# NODE_MCU_V2.net
KiCad netlist of a schematic drawn in Altium Designer
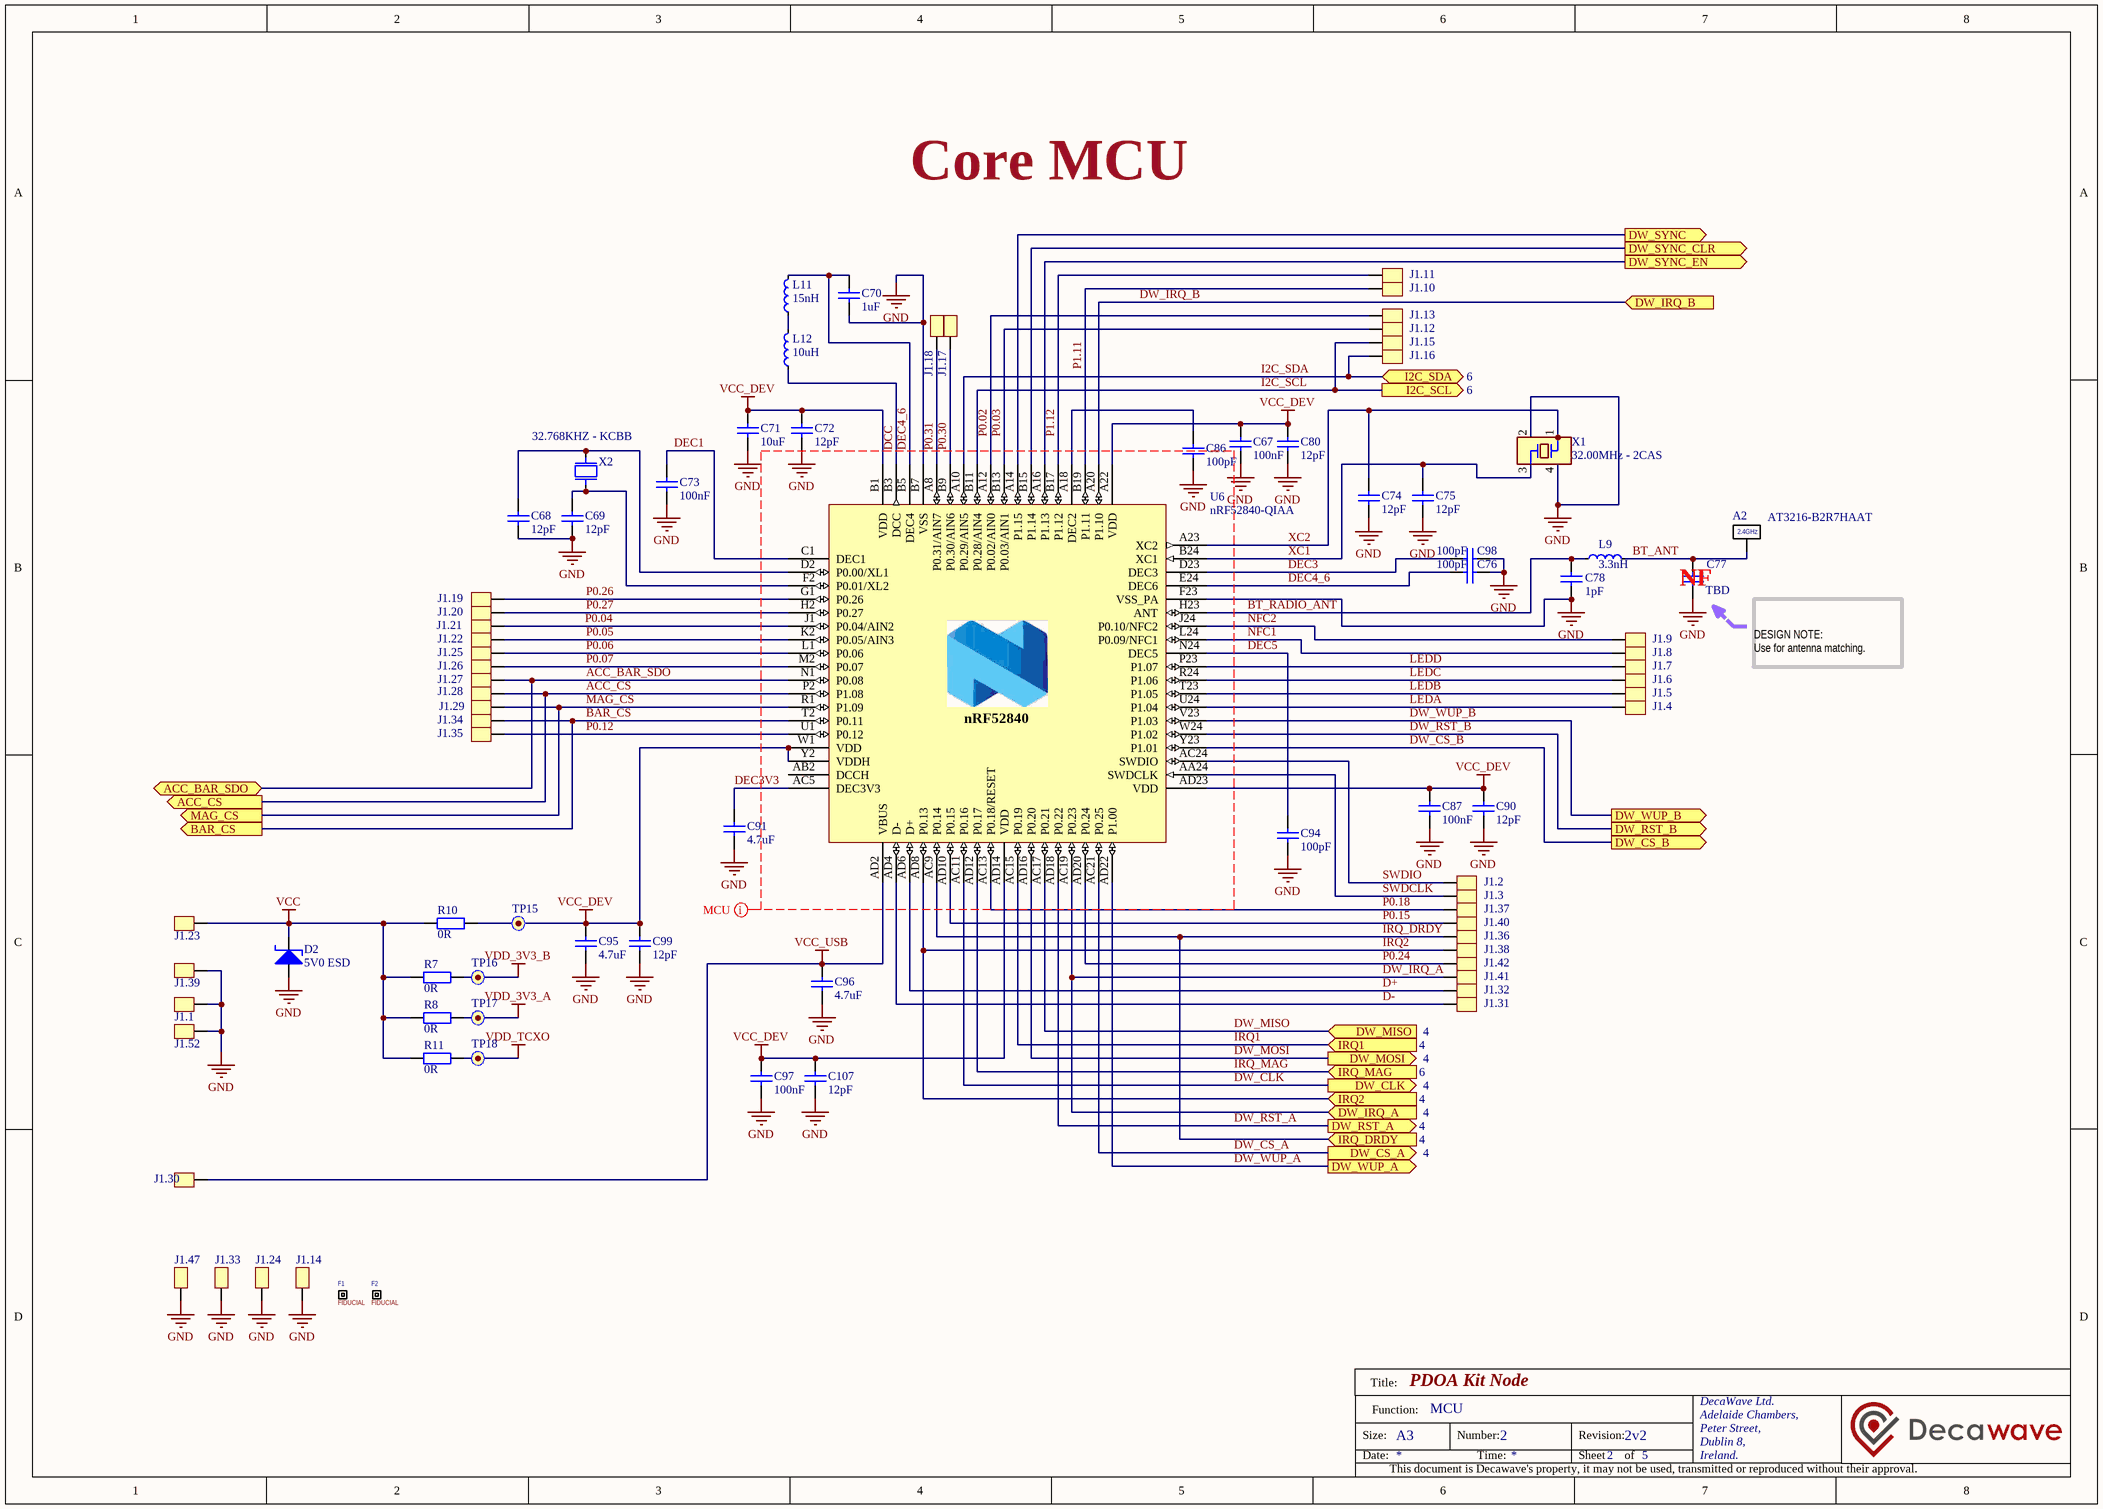
[diagram p0: NODE_MCU_V2.SchDoc]

(export (version "E")
  (design (tool "Eeschema 10.0.6"))
  (components
    (comp (ref "A2")
      (value "AT3216-B2R7HAAT")
      (footprint "AT3216")
      (description "CHIP, 2.45GHZ, 50 OHM, 3.2x1.6 ACX - AAT3216-B2R7HAAT- ANTENNA")
      (fields
        (field (name "MANUFACTURER") "ACX")
        (field (name "MANUFACTURER PART NUMBER") "AMCA31-2R450G-S1F-T")
      )
      (libsource (lib "drak_Library") (part "AT3216-B2R7HAAT"))
    )
    (comp (ref "C67")
      (value "100nF")
      (footprint "C0201")
      (description "100nF_0201_10%")
      (fields
        (field (name "MANUFACTURER") "Murata Electronics North America")
        (field (name "MANUFACTURER PART NUMBER") "GRM033C81E104KE14D")
      )
      (libsource (lib "drak_Library") (part "GRM033C81E104ME14D"))
    )
    (comp (ref "C68")
      (value "12pF")
      (footprint "C0201")
      (description "12pF_0201_1%")
      (fields
        (field (name "MANUFACTURER") "Murata Electronics North America")
        (field (name "MANUFACTURER PART NUMBER") "GRM0335C1E120JA01D")
      )
      (libsource (lib "drak_Library") (part "GRM0335C1E120JA01D"))
    )
    (comp (ref "C69")
      (value "12pF")
      (footprint "C0201")
      (description "12pF_0201_1%")
      (fields
        (field (name "MANUFACTURER") "Murata Electronics North America")
        (field (name "MANUFACTURER PART NUMBER") "GRM0335C1E120JA01D")
      )
      (libsource (lib "drak_Library") (part "GRM0335C1E120JA01D"))
    )
    (comp (ref "C70")
      (value "1uF")
      (footprint "C0402")
      (description "CAP CER 1UF 10V X5R 0402")
      (fields
        (field (name "MANUFACTURER") "Murata Electronics North America")
        (field (name "MANUFACTURER PART NUMBER") "GRM155R61A105KE15D")
      )
      (libsource (lib "drak_Library") (part "GRM155R61A105KE15D"))
    )
    (comp (ref "C71")
      (value "10uF")
      (footprint "C0603")
      (description "CAP CER 10UF 6.3V X5R 0603")
      (fields
        (field (name "MANUFACTURER") "Murata Electronics North America")
        (field (name "MANUFACTURER PART NUMBER") "GRM188R60J106ME47D")
      )
      (libsource (lib "drak_Library") (part "GRM188R60J106ME84D"))
    )
    (comp (ref "C72")
      (value "12pF")
      (footprint "C0201")
      (description "12pF_0201_1%")
      (fields
        (field (name "MANUFACTURER") "Murata Electronics North America")
        (field (name "MANUFACTURER PART NUMBER") "GRM0335C1E120JA01D")
      )
      (libsource (lib "drak_Library") (part "GRM0335C1E120JA01D"))
    )
    (comp (ref "C73")
      (value "100nF")
      (footprint "C0201")
      (description "100nF_0201_10%")
      (fields
        (field (name "MANUFACTURER") "Murata Electronics North America")
        (field (name "MANUFACTURER PART NUMBER") "GRM033C81E104KE14D")
      )
      (libsource (lib "drak_Library") (part "GRM033C81E104ME14D"))
    )
    (comp (ref "C74")
      (value "12pF")
      (footprint "C0201")
      (description "12pF_0201_1%")
      (fields
        (field (name "MANUFACTURER") "Murata Electronics North America")
        (field (name "MANUFACTURER PART NUMBER") "GRM0335C1E120JA01D")
      )
      (libsource (lib "drak_Library") (part "GRM0335C1E120JA01D"))
    )
    (comp (ref "C75")
      (value "12pF")
      (footprint "C0201")
      (description "12pF_0201_1%")
      (fields
        (field (name "MANUFACTURER") "Murata Electronics North America")
        (field (name "MANUFACTURER PART NUMBER") "GRM0335C1E120JA01D")
      )
      (libsource (lib "drak_Library") (part "GRM0335C1E120JA01D"))
    )
    (comp (ref "C76")
      (value "100pF")
      (footprint "C0201")
      (description "CAP CER 100PF 25V NP0 0201")
      (fields
        (field (name "MANUFACTURER") "Murata Electronics North America")
        (field (name "MANUFACTURER PART NUMBER") "GRM0335C1E101JA01D")
      )
      (libsource (lib "drak_Library") (part "GRM0335C1E101JA01D"))
    )
    (comp (ref "C77")
      (value "TBD")
      (footprint "C0201")
      (description "CAP CER 1PF 50V NP0 0201")
      (fields
        (field (name "MANUFACTURER") "Murata Electronics North America")
        (field (name "MANUFACTURER PART NUMBER") "GRM0335C1H1R0BA01D")
      )
      (libsource (lib "drak_Library") (part "GRM0335C1H1R0BA01D"))
    )
    (comp (ref "C78")
      (value "1pF")
      (footprint "C0201")
      (description "CAP CER 1PF 50V NP0 0201")
      (fields
        (field (name "MANUFACTURER") "Murata Electronics North America")
        (field (name "MANUFACTURER PART NUMBER") "GRM0335C1H1R0BA01D")
      )
      (libsource (lib "drak_Library") (part "GRM0335C1H1R0BA01D"))
    )
    (comp (ref "C80")
      (value "12pF")
      (footprint "C0201")
      (description "12pF_0201_1%")
      (fields
        (field (name "MANUFACTURER") "Murata Electronics North America")
        (field (name "MANUFACTURER PART NUMBER") "GRM0335C1E120JA01D")
      )
      (libsource (lib "drak_Library") (part "GRM0335C1E120JA01D"))
    )
    (comp (ref "C86")
      (value "100pF")
      (footprint "C0201")
      (description "CAP CER 100PF 25V NP0 0201")
      (fields
        (field (name "MANUFACTURER") "Murata Electronics North America")
        (field (name "MANUFACTURER PART NUMBER") "GRM0335C1E101JA01D")
      )
      (libsource (lib "drak_Library") (part "GRM0335C1E101JA01D"))
    )
    (comp (ref "C87")
      (value "100nF")
      (footprint "C0201")
      (description "100nF_0201_10%")
      (fields
        (field (name "MANUFACTURER") "Murata Electronics North America")
        (field (name "MANUFACTURER PART NUMBER") "GRM033C81E104KE14D")
      )
      (libsource (lib "drak_Library") (part "GRM033C81E104ME14D"))
    )
    (comp (ref "C90")
      (value "12pF")
      (footprint "C0201")
      (description "12pF_0201_1%")
      (fields
        (field (name "MANUFACTURER") "Murata Electronics North America")
        (field (name "MANUFACTURER PART NUMBER") "GRM0335C1E120JA01D")
      )
      (libsource (lib "drak_Library") (part "GRM0335C1E120JA01D"))
    )
    (comp (ref "C91")
      (value "4.7uF")
      (footprint "C0603")
      (description "CAP CER 4.7UF 6.3V X5R 0603")
      (fields
        (field (name "MANUFACTURER") "SamSung")
        (field (name "MANUFACTURER PART NUMBER") "CL10A475KQ8NNN#")
      )
      (libsource (lib "drak_Library") (part "GRM188R60J106ME84D"))
    )
    (comp (ref "C94")
      (value "100pF")
      (footprint "C0201")
      (description "CAP CER 100PF 25V NP0 0201")
      (fields
        (field (name "MANUFACTURER") "Murata Electronics North America")
        (field (name "MANUFACTURER PART NUMBER") "GRM0335C1E101JA01D")
      )
      (libsource (lib "drak_Library") (part "GRM0335C1E101JA01D"))
    )
    (comp (ref "C95")
      (value "4.7uF")
      (footprint "C0603")
      (description "CAP CER 4.7UF 6.3V X5R 0603")
      (fields
        (field (name "MANUFACTURER") "SamSung")
        (field (name "MANUFACTURER PART NUMBER") "CL10A475KQ8NNN#")
      )
      (libsource (lib "drak_Library") (part "GRM188R60J106ME84D"))
    )
    (comp (ref "C96")
      (value "4.7uF")
      (footprint "C0603")
      (description "CAP CER 4.7UF 6.3V X5R 0603")
      (fields
        (field (name "MANUFACTURER") "SamSung")
        (field (name "MANUFACTURER PART NUMBER") "CL10A475KQ8NNN#")
      )
      (libsource (lib "drak_Library") (part "GRM188R60J106ME84D"))
    )
    (comp (ref "C97")
      (value "100nF")
      (footprint "C0201")
      (description "100nF_0201_10%")
      (fields
        (field (name "MANUFACTURER") "Murata Electronics North America")
        (field (name "MANUFACTURER PART NUMBER") "GRM033C81E104KE14D")
      )
      (libsource (lib "drak_Library") (part "GRM033C81E104ME14D"))
    )
    (comp (ref "C98")
      (value "100pF")
      (footprint "C0201")
      (description "CAP CER 100PF 25V NP0 0201")
      (fields
        (field (name "MANUFACTURER") "Murata Electronics North America")
        (field (name "MANUFACTURER PART NUMBER") "GRM0335C1E101JA01D")
      )
      (libsource (lib "drak_Library") (part "GRM0335C1E101JA01D"))
    )
    (comp (ref "C99")
      (value "12pF")
      (footprint "C0201")
      (description "12pF_0201_1%")
      (fields
        (field (name "MANUFACTURER") "Murata Electronics North America")
        (field (name "MANUFACTURER PART NUMBER") "GRM0335C1E120JA01D")
      )
      (libsource (lib "drak_Library") (part "GRM0335C1E120JA01D"))
    )
    (comp (ref "C107")
      (value "12pF")
      (footprint "C0201")
      (description "12pF_0201_1%")
      (fields
        (field (name "MANUFACTURER") "Murata Electronics North America")
        (field (name "MANUFACTURER PART NUMBER") "GRM0335C1E120JA01D")
      )
      (libsource (lib "drak_Library") (part "GRM0335C1E120JA01D"))
    )
    (comp (ref "D2")
      (value "5V0 ESD")
      (footprint "DFN65P100X40-2N")
      (description "TVS DIODE 5VWM")
      (fields
        (field (name "MANUFACTURER") "Toshiba Semiconductor and Storage")
        (field (name "MANUFACTURER PART NUMBER") "DF2S6.2CT,L3F")
      )
      (libsource (lib "drak_Library") (part "DF2S6.2CT,L3F"))
    )
    (comp (ref "F1")
      (value "FIDUCIAL")
      (footprint "FID1")
      (description "Fiducial 1mm")
      (libsource (lib "drak_Library") (part "FID1"))
    )
    (comp (ref "F2")
      (value "FIDUCIAL")
      (footprint "FID1")
      (description "Fiducial 1mm")
      (libsource (lib "drak_Library") (part "FID1"))
    )
    (comp (ref "J1.1")
      (value "EDGE_PIN")
      (footprint "PCB_EDGE_1MM")
      (description "PCB Edge pin")
      (libsource (lib "DrakSchlib") (part "EDGE_PIN"))
    )
    (comp (ref "J1.2")
      (value "EDGE_PIN")
      (footprint "PCB_EDGE_1MM")
      (description "PCB Edge pin")
      (libsource (lib "") (part "PCB_EDGE_1MM_1"))
    )
    (comp (ref "J1.3")
      (value "EDGE_PIN")
      (footprint "PCB_EDGE_1MM")
      (description "PCB Edge pin")
      (libsource (lib "") (part "PCB_EDGE_1MM_1"))
    )
    (comp (ref "J1.4")
      (value "EDGE_PIN")
      (footprint "PCB_EDGE_1MM")
      (description "PCB Edge pin")
      (libsource (lib "drak_Library") (part "PCB_EDGE_1MM"))
    )
    (comp (ref "J1.5")
      (value "EDGE_PIN")
      (footprint "PCB_EDGE_1MM")
      (description "PCB Edge pin")
      (libsource (lib "drak_Library") (part "PCB_EDGE_1MM"))
    )
    (comp (ref "J1.6")
      (value "EDGE_PIN")
      (footprint "PCB_EDGE_1MM")
      (description "PCB Edge pin")
      (libsource (lib "drak_Library") (part "PCB_EDGE_1MM"))
    )
    (comp (ref "J1.7")
      (value "EDGE_PIN")
      (footprint "PCB_EDGE_1MM")
      (description "PCB Edge pin")
      (libsource (lib "drak_Library") (part "PCB_EDGE_1MM"))
    )
    (comp (ref "J1.8")
      (value "EDGE_PIN")
      (footprint "PCB_EDGE_1MM")
      (description "PCB Edge pin")
      (libsource (lib "") (part "PCB_EDGE_1MM_1"))
    )
    (comp (ref "J1.9")
      (value "EDGE_PIN")
      (footprint "PCB_EDGE_1MM")
      (description "PCB Edge pin")
      (libsource (lib "") (part "PCB_EDGE_1MM_1"))
    )
    (comp (ref "J1.10")
      (value "EDGE_PIN")
      (footprint "PCB_EDGE_1MM")
      (description "PCB Edge pin")
      (libsource (lib "drak_Library") (part "PCB_EDGE_1MM"))
    )
    (comp (ref "J1.11")
      (value "EDGE_PIN")
      (footprint "PCB_EDGE_1MM")
      (description "PCB Edge pin")
      (libsource (lib "drak_Library") (part "PCB_EDGE_1MM"))
    )
    (comp (ref "J1.12")
      (value "EDGE_PIN")
      (footprint "PCB_EDGE_1MM")
      (description "PCB Edge pin")
      (libsource (lib "drak_Library") (part "PCB_EDGE_1MM"))
    )
    (comp (ref "J1.13")
      (value "EDGE_PIN")
      (footprint "PCB_EDGE_1MM")
      (description "PCB Edge pin")
      (libsource (lib "drak_Library") (part "PCB_EDGE_1MM"))
    )
    (comp (ref "J1.14")
      (value "EDGE_PIN")
      (footprint "PCB_EDGE_1MM")
      (description "PCB Edge pin")
      (libsource (lib "drak_Library") (part "PCB_EDGE_1MM"))
    )
    (comp (ref "J1.15")
      (value "EDGE_PIN")
      (footprint "PCB_EDGE_1MM")
      (description "PCB Edge pin")
      (libsource (lib "drak_Library") (part "PCB_EDGE_1MM"))
    )
    (comp (ref "J1.16")
      (value "EDGE_PIN")
      (footprint "PCB_EDGE_1MM")
      (description "PCB Edge pin")
      (libsource (lib "drak_Library") (part "PCB_EDGE_1MM"))
    )
    (comp (ref "J1.17")
      (value "EDGE_PIN")
      (footprint "PCB_EDGE_1MM")
      (description "PCB Edge pin")
      (libsource (lib "drak_Library") (part "PCB_EDGE_1MM"))
    )
    (comp (ref "J1.18")
      (value "EDGE_PIN")
      (footprint "PCB_EDGE_1MM")
      (description "PCB Edge pin")
      (libsource (lib "drak_Library") (part "PCB_EDGE_1MM"))
    )
    (comp (ref "J1.19")
      (value "EDGE_PIN")
      (footprint "PCB_EDGE_1MM")
      (description "PCB Edge pin")
      (libsource (lib "DrakSchlib") (part "EDGE_PIN"))
    )
    (comp (ref "J1.20")
      (value "EDGE_PIN")
      (footprint "PCB_EDGE_1MM")
      (description "PCB Edge pin")
      (libsource (lib "") (part "PCB_EDGE_1MM_3"))
    )
    (comp (ref "J1.21")
      (value "EDGE_PIN")
      (footprint "PCB_EDGE_1MM")
      (description "PCB Edge pin")
      (libsource (lib "") (part "PCB_EDGE_1MM_2"))
    )
    (comp (ref "J1.22")
      (value "EDGE_PIN")
      (footprint "PCB_EDGE_1MM")
      (description "PCB Edge pin")
      (libsource (lib "DrakSchlib") (part "EDGE_PIN"))
    )
    (comp (ref "J1.23")
      (value "EDGE_PIN")
      (footprint "PCB_EDGE_1MM")
      (description "PCB Edge pin")
      (libsource (lib "DrakSchlib") (part "EDGE_PIN"))
    )
    (comp (ref "J1.24")
      (value "EDGE_PIN")
      (footprint "PCB_EDGE_1MM")
      (description "PCB Edge pin")
      (libsource (lib "drak_Library") (part "PCB_EDGE_1MM"))
    )
    (comp (ref "J1.25")
      (value "EDGE_PIN")
      (footprint "PCB_EDGE_1MM")
      (description "PCB Edge pin")
      (libsource (lib "") (part "PCB_EDGE_1MM_2"))
    )
    (comp (ref "J1.26")
      (value "EDGE_PIN")
      (footprint "PCB_EDGE_1MM")
      (description "PCB Edge pin")
      (libsource (lib "") (part "PCB_EDGE_1MM_3"))
    )
    (comp (ref "J1.27")
      (value "EDGE_PIN")
      (footprint "PCB_EDGE_1MM")
      (description "PCB Edge pin")
      (libsource (lib "") (part "PCB_EDGE_1MM_3"))
    )
    (comp (ref "J1.28")
      (value "EDGE_PIN")
      (footprint "PCB_EDGE_1MM")
      (description "PCB Edge pin")
      (libsource (lib "") (part "PCB_EDGE_1MM_2"))
    )
    (comp (ref "J1.29")
      (value "EDGE_PIN")
      (footprint "PCB_EDGE_1MM")
      (description "PCB Edge pin")
      (libsource (lib "") (part "PCB_EDGE_1MM_2"))
    )
    (comp (ref "J1.30")
      (value "EDGE_PIN")
      (footprint "PCB_EDGE_1MM")
      (description "PCB Edge pin")
      (libsource (lib "DrakSchlib") (part "EDGE_PIN"))
    )
    (comp (ref "J1.31")
      (value "EDGE_PIN")
      (footprint "PCB_EDGE_1MM")
      (description "PCB Edge pin")
      (libsource (lib "") (part "PCB_EDGE_1MM_1"))
    )
    (comp (ref "J1.32")
      (value "EDGE_PIN")
      (footprint "PCB_EDGE_1MM")
      (description "PCB Edge pin")
      (libsource (lib "") (part "PCB_EDGE_1MM_1"))
    )
    (comp (ref "J1.33")
      (value "EDGE_PIN")
      (footprint "PCB_EDGE_1MM")
      (description "PCB Edge pin")
      (libsource (lib "drak_Library") (part "PCB_EDGE_1MM"))
    )
    (comp (ref "J1.34")
      (value "EDGE_PIN")
      (footprint "PCB_EDGE_1MM")
      (description "PCB Edge pin")
      (libsource (lib "") (part "PCB_EDGE_1MM_2"))
    )
    (comp (ref "J1.35")
      (value "EDGE_PIN")
      (footprint "PCB_EDGE_1MM")
      (description "PCB Edge pin")
      (libsource (lib "DrakSchlib") (part "EDGE_PIN"))
    )
    (comp (ref "J1.36")
      (value "EDGE_PIN")
      (footprint "PCB_EDGE_1MM")
      (description "PCB Edge pin")
      (libsource (lib "") (part "PCB_EDGE_1MM_1"))
    )
    (comp (ref "J1.37")
      (value "EDGE_PIN")
      (footprint "PCB_EDGE_1MM")
      (description "PCB Edge pin")
      (libsource (lib "") (part "PCB_EDGE_1MM_1"))
    )
    (comp (ref "J1.38")
      (value "EDGE_PIN")
      (footprint "PCB_EDGE_1MM")
      (description "PCB Edge pin")
      (libsource (lib "") (part "PCB_EDGE_1MM_1"))
    )
    (comp (ref "J1.39")
      (value "EDGE_PIN")
      (footprint "PCB_EDGE_1MM")
      (description "PCB Edge pin")
      (libsource (lib "DrakSchlib") (part "EDGE_PIN"))
    )
    (comp (ref "J1.40")
      (value "EDGE_PIN")
      (footprint "PCB_EDGE_1MM")
      (description "PCB Edge pin")
      (libsource (lib "") (part "PCB_EDGE_1MM_1"))
    )
    (comp (ref "J1.41")
      (value "EDGE_PIN")
      (footprint "PCB_EDGE_1MM")
      (description "PCB Edge pin")
      (libsource (lib "") (part "PCB_EDGE_1MM_1"))
    )
    (comp (ref "J1.42")
      (value "EDGE_PIN")
      (footprint "PCB_EDGE_1MM")
      (description "PCB Edge pin")
      (libsource (lib "") (part "PCB_EDGE_1MM_1"))
    )
    (comp (ref "J1.47")
      (value "EDGE_PIN")
      (footprint "PCB_EDGE_1MM")
      (description "PCB Edge pin")
      (libsource (lib "drak_Library") (part "PCB_EDGE_1MM"))
    )
    (comp (ref "J1.52")
      (value "EDGE_PIN")
      (footprint "PCB_EDGE_1MM")
      (description "PCB Edge pin")
      (libsource (lib "DrakSchlib") (part "EDGE_PIN"))
    )
    (comp (ref "L9")
      (value "3.3nH")
      (footprint "L0201")
      (description "FIXED IND 3.3NH 400MA 320 MOHM")
      (fields
        (field (name "MANUFACTURER") "Murata Electronics North America")
        (field (name "MANUFACTURER PART NUMBER") "LQP03TG3N3C02D")
      )
      (libsource (lib "drak_Library") (part "LQP03TG3N3C02D"))
    )
    (comp (ref "L11")
      (value "15nH")
      (footprint "INDC1005X05N")
      (description "FIXED IND 15NH 320MA 460 MOHM")
      (fields
        (field (name "MANUFACTURER") "Taiyo Yuden")
        (field (name "MANUFACTURER PART NUMBER") "HK100515NJ-T")
      )
      (libsource (lib "Schlib1") (part "HK100515NJ-T"))
    )
    (comp (ref "L12")
      (value "10uH")
      (footprint "L0603")
      (description "FIXED IND 10UH 80MA 360 MOHM SMD")
      (fields
        (field (name "MANUFACTURER") "Taiyo Yuden")
        (field (name "MANUFACTURER PART NUMBER") "LBMF1608T100K")
      )
      (libsource (lib "drak_Library") (part "LBMF1608T100K"))
    )
    (comp (ref "R7")
      (value "0R")
      (footprint "R0201")
      (description "RES SMD 0.0OHM JUMPER 1/20W 0201")
      (fields
        (field (name "MANUFACTURER") "Yageo")
        (field (name "MANUFACTURER PART NUMBER") "RC0201JR-070RL")
      )
      (libsource (lib "drak_Library") (part "RC0201JR-070RL"))
    )
    (comp (ref "R8")
      (value "0R")
      (footprint "R0402 -RF")
      (description "RES SMD 0.0OHM JUMPER 1/20W 0402")
      (fields
        (field (name "MANUFACTURER") "Yageo")
        (field (name "MANUFACTURER PART NUMBER") "RC0402JR-070RL")
      )
      (libsource (lib "drak_Library") (part "RC0201JR-070RL"))
    )
    (comp (ref "R10")
      (value "0R")
      (footprint "R0201")
      (description "RES SMD 0.0OHM JUMPER 1/20W 0201")
      (fields
        (field (name "MANUFACTURER") "Yageo")
        (field (name "MANUFACTURER PART NUMBER") "RC0201JR-070RL")
      )
      (libsource (lib "drak_Library") (part "RC0201JR-070RL"))
    )
    (comp (ref "R11")
      (value "0R")
      (footprint "R0201")
      (description "RES SMD 0.0OHM JUMPER 1/20W 0201")
      (fields
        (field (name "MANUFACTURER") "Yageo")
        (field (name "MANUFACTURER PART NUMBER") "RC0201JR-070RL")
      )
      (libsource (lib "drak_Library") (part "RC0201JR-070RL"))
    )
    (comp (ref "TP15")
      (value "TP")
      (footprint "TP_40S")
      (description "test point")
      (libsource (lib "AoAB") (part "TP"))
    )
    (comp (ref "TP16")
      (value "TP")
      (footprint "TP_40S")
      (description "test point")
      (libsource (lib "AoAB") (part "TP"))
    )
    (comp (ref "TP17")
      (value "TP")
      (footprint "TP_40S")
      (description "test point")
      (libsource (lib "AoAB") (part "TP"))
    )
    (comp (ref "TP18")
      (value "TP")
      (footprint "TP_40S")
      (description "test point")
      (libsource (lib "AoAB") (part "TP"))
    )
    (comp (ref "U6")
      (value "nRF52840-QIAA")
      (footprint "AQFN50P700X700X85_HS-74N")
      (description "Multi-protocol Bluetooth Low Energy, IEEE 802.15.4, ANT and 2.4GHz proprietary system-on-chip")
      (fields (field (name "MANUFACTURER") "Nordic Semiconductor ASA"))
      (libsource (lib "NODE_V2") (part "nRF52840_QIAA"))
    )
    (comp (ref "X1")
      (value "32.00MHz - 2CAS")
      (footprint "ABM10")
      (description "CRYSTAL 32MHZ 8PF SMD")
      (fields (field (name "MANUFACTURER") "Commutek") (field (name "MANUFACTURER PART NUMBER") "2CAS"))
      (libsource (lib "drak_Library") (part "ABM10"))
    )
    (comp (ref "X2")
      (value "32.768KHZ - KCBB")
      (footprint "XTAL_SMD_3.2X1.5MM")
      (description "CRYSTAL 32.7680KHZ 12.5PF SMD")
      (fields (field (name "MANUFACTURER") "Commutek") (field (name "MANUFACTURER PART NUMBER") "KCBB"))
      (libsource (lib "drak_Library") (part "ABS06-32.768KHZ-T"))
    )
  )
  (nets
    (net (code "1") (name "/ACC_BAR_SDO") (class "Default")
      (node (ref "J1.27") (pin "0") (pinfunction "0_0") (pintype "passive"))
      (node (ref "U6") (pin "N1") (pinfunction "P0.08_N1") (pintype "bidirectional"))
    )
    (net (code "2") (name "/ACC_CS") (class "Default")
      (node (ref "J1.28") (pin "0") (pinfunction "0_0") (pintype "passive"))
      (node (ref "U6") (pin "P2") (pinfunction "P1.08_P2") (pintype "bidirectional"))
    )
    (net (code "3") (name "/BAR_CS") (class "Default")
      (node (ref "J1.34") (pin "0") (pinfunction "0_0") (pintype "passive"))
      (node (ref "U6") (pin "T2") (pinfunction "P0.11_T2") (pintype "bidirectional"))
    )
    (net (code "4") (name "/BT_ANT") (class "Default")
      (node (ref "A2") (pin "1") (pintype "passive"))
      (node (ref "C77") (pin "2") (pinfunction "2_2") (pintype "passive"))
      (node (ref "L9") (pin "2") (pinfunction "2_2") (pintype "passive"))
    )
    (net (code "5") (name "/BT_RADIO_ANT") (class "Default")
      (node (ref "C78") (pin "2") (pinfunction "2_2") (pintype "passive"))
      (node (ref "L9") (pin "1") (pinfunction "1_1") (pintype "passive"))
      (node (ref "U6") (pin "H23") (pinfunction "ANT_H23") (pintype "bidirectional"))
    )
    (net (code "6") (name "/D+") (class "Default")
      (node (ref "J1.32") (pin "0") (pinfunction "0_0") (pintype "passive"))
      (node (ref "U6") (pin "AD6") (pinfunction "D+_AD6") (pintype "bidirectional"))
    )
    (net (code "7") (name "/D-") (class "Default")
      (node (ref "J1.31") (pin "0") (pinfunction "0_0") (pintype "passive"))
      (node (ref "U6") (pin "AD4") (pinfunction "D-_AD4") (pintype "bidirectional"))
    )
    (net (code "8") (name "/DCC") (class "Default")
      (node (ref "L12") (pin "1") (pinfunction "1_1") (pintype "passive"))
      (node (ref "U6") (pin "B3") (pinfunction "DCC_B3") (pintype "output"))
    )
    (net (code "9") (name "/DEC1") (class "Default")
      (node (ref "C73") (pin "2") (pinfunction "2_2") (pintype "passive"))
      (node (ref "U6") (pin "C1") (pinfunction "DEC1_C1") (pintype "power_in"))
    )
    (net (code "10") (name "/DEC3") (class "Default")
      (node (ref "C98") (pin "2") (pinfunction "2_2") (pintype "passive"))
      (node (ref "U6") (pin "D23") (pinfunction "DEC3_D23") (pintype "power_in"))
    )
    (net (code "11") (name "/DEC3V3") (class "Default")
      (node (ref "C91") (pin "2") (pinfunction "2_2") (pintype "passive"))
      (node (ref "U6") (pin "AC5") (pinfunction "DEC3V3_AC5") (pintype "power_in"))
    )
    (net (code "12") (name "/DEC4_6") (class "Default")
      (node (ref "C70") (pin "2") (pinfunction "2_2") (pintype "passive"))
      (node (ref "C76") (pin "2") (pinfunction "2_2") (pintype "passive"))
      (node (ref "L11") (pin "2") (pinfunction "2_2") (pintype "passive"))
      (node (ref "U6") (pin "B5") (pinfunction "DEC4_B5") (pintype "power_in"))
      (node (ref "U6") (pin "E24") (pinfunction "DEC6_E24") (pintype "power_in"))
    )
    (net (code "13") (name "/DEC5") (class "Default")
      (node (ref "C94") (pin "2") (pinfunction "2_2") (pintype "passive"))
      (node (ref "U6") (pin "N24") (pinfunction "DEC5_N24") (pintype "power_in"))
    )
    (net (code "14") (name "/DW_CLK") (class "Default")
      (node (ref "U6") (pin "AC11") (pinfunction "P0.16_AC11") (pintype "bidirectional"))
    )
    (net (code "15") (name "/DW_CS_A") (class "Default")
      (node (ref "U6") (pin "AC21") (pinfunction "P0.25_AC21") (pintype "bidirectional"))
    )
    (net (code "16") (name "/DW_CS_B") (class "Default")
      (node (ref "U6") (pin "Y23") (pinfunction "P1.01_Y23") (pintype "bidirectional"))
    )
    (net (code "17") (name "/DW_IRQ_A") (class "Default")
      (node (ref "J1.41") (pin "0") (pinfunction "0_0") (pintype "passive"))
      (node (ref "U6") (pin "AC19") (pinfunction "P0.23_AC19") (pintype "bidirectional"))
    )
    (net (code "18") (name "/DW_IRQ_B") (class "Default")
      (node (ref "U6") (pin "A20") (pinfunction "P1.10_A20") (pintype "bidirectional"))
    )
    (net (code "19") (name "/DW_MISO") (class "Default")
      (node (ref "U6") (pin "AC17") (pinfunction "P0.21_AC17") (pintype "bidirectional"))
    )
    (net (code "20") (name "/DW_MOSI") (class "Default")
      (node (ref "U6") (pin "AD16") (pinfunction "P0.20_AD16") (pintype "bidirectional"))
    )
    (net (code "21") (name "/DW_RST_A") (class "Default")
      (node (ref "U6") (pin "AD18") (pinfunction "P0.22_AD18") (pintype "bidirectional"))
    )
    (net (code "22") (name "/DW_RST_B") (class "Default")
      (node (ref "U6") (pin "W24") (pinfunction "P1.02_W24") (pintype "bidirectional"))
    )
    (net (code "23") (name "/DW_SYNC") (class "Default")
      (node (ref "U6") (pin "A14") (pinfunction "P1.15_A14") (pintype "bidirectional"))
    )
    (net (code "24") (name "/DW_SYNC_CLR") (class "Default")
      (node (ref "U6") (pin "B15") (pinfunction "P1.14_B15") (pintype "bidirectional"))
    )
    (net (code "25") (name "/DW_SYNC_EN") (class "Default")
      (node (ref "U6") (pin "A16") (pinfunction "P1.13_A16") (pintype "bidirectional"))
    )
    (net (code "26") (name "/DW_WUP_A") (class "Default")
      (node (ref "U6") (pin "AD22") (pinfunction "P1.00_AD22") (pintype "bidirectional"))
    )
    (net (code "27") (name "/DW_WUP_B") (class "Default")
      (node (ref "U6") (pin "V23") (pinfunction "P1.03_V23") (pintype "bidirectional"))
    )
    (net (code "28") (name "/I2C_SCL") (class "Default")
      (node (ref "J1.15") (pin "0") (pinfunction "0_0") (pintype "passive"))
      (node (ref "U6") (pin "B11") (pinfunction "P0.28/AIN4_B11") (pintype "bidirectional"))
    )
    (net (code "29") (name "/I2C_SDA") (class "Default")
      (node (ref "J1.16") (pin "0") (pinfunction "0_0") (pintype "passive"))
      (node (ref "U6") (pin "A10") (pinfunction "P0.29/AIN5_A10") (pintype "bidirectional"))
    )
    (net (code "30") (name "/IRQ1") (class "Default")
      (node (ref "U6") (pin "AC15") (pinfunction "P0.19_AC15") (pintype "bidirectional"))
    )
    (net (code "31") (name "/IRQ2") (class "Default")
      (node (ref "J1.38") (pin "0") (pinfunction "0_0") (pintype "passive"))
      (node (ref "U6") (pin "AD8") (pinfunction "P0.13_AD8") (pintype "bidirectional"))
    )
    (net (code "32") (name "/IRQ_DRDY") (class "Default")
      (node (ref "J1.36") (pin "0") (pinfunction "0_0") (pintype "passive"))
      (node (ref "U6") (pin "AC9") (pinfunction "P0.14_AC9") (pintype "bidirectional"))
    )
    (net (code "33") (name "/IRQ_MAG") (class "Default")
      (node (ref "U6") (pin "AD12") (pinfunction "P0.17_AD12") (pintype "bidirectional"))
    )
    (net (code "34") (name "/LEDA") (class "Default")
      (node (ref "J1.4") (pin "0") (pinfunction "0_0") (pintype "passive"))
      (node (ref "U6") (pin "U24") (pinfunction "P1.04_U24") (pintype "bidirectional"))
    )
    (net (code "35") (name "/LEDB") (class "Default")
      (node (ref "J1.5") (pin "0") (pinfunction "0_0") (pintype "passive"))
      (node (ref "U6") (pin "T23") (pinfunction "P1.05_T23") (pintype "bidirectional"))
    )
    (net (code "36") (name "/LEDC") (class "Default")
      (node (ref "J1.6") (pin "0") (pinfunction "0_0") (pintype "passive"))
      (node (ref "U6") (pin "R24") (pinfunction "P1.06_R24") (pintype "bidirectional"))
    )
    (net (code "37") (name "/LEDD") (class "Default")
      (node (ref "J1.7") (pin "0") (pinfunction "0_0") (pintype "passive"))
      (node (ref "U6") (pin "P23") (pinfunction "P1.07_P23") (pintype "bidirectional"))
    )
    (net (code "38") (name "/MAG_CS") (class "Default")
      (node (ref "J1.29") (pin "0") (pinfunction "0_0") (pintype "passive"))
      (node (ref "U6") (pin "R1") (pinfunction "P1.09_R1") (pintype "bidirectional"))
    )
    (net (code "39") (name "/NFC1") (class "Default")
      (node (ref "J1.8") (pin "0") (pinfunction "0_0") (pintype "passive"))
      (node (ref "U6") (pin "L24") (pinfunction "P0.09/NFC1_L24") (pintype "bidirectional"))
    )
    (net (code "40") (name "/NFC2") (class "Default")
      (node (ref "J1.9") (pin "0") (pinfunction "0_0") (pintype "passive"))
      (node (ref "U6") (pin "J24") (pinfunction "P0.10/NFC2_J24") (pintype "bidirectional"))
    )
    (net (code "41") (name "/P0.02") (class "Default")
      (node (ref "J1.13") (pin "0") (pinfunction "0_0") (pintype "passive"))
      (node (ref "U6") (pin "A12") (pinfunction "P0.02/AIN0_A12") (pintype "bidirectional"))
    )
    (net (code "42") (name "/P0.03") (class "Default")
      (node (ref "J1.12") (pin "0") (pinfunction "0_0") (pintype "passive"))
      (node (ref "U6") (pin "B13") (pinfunction "P0.03/AIN1_B13") (pintype "bidirectional"))
    )
    (net (code "43") (name "/P0.04") (class "Default")
      (node (ref "J1.21") (pin "0") (pinfunction "0_0") (pintype "passive"))
      (node (ref "U6") (pin "J1") (pinfunction "P0.04/AIN2_J1") (pintype "bidirectional"))
    )
    (net (code "44") (name "/P0.05") (class "Default")
      (node (ref "J1.22") (pin "0") (pinfunction "0_0") (pintype "passive"))
      (node (ref "U6") (pin "K2") (pinfunction "P0.05/AIN3_K2") (pintype "bidirectional"))
    )
    (net (code "45") (name "/P0.06") (class "Default")
      (node (ref "J1.25") (pin "0") (pinfunction "0_0") (pintype "passive"))
      (node (ref "U6") (pin "L1") (pinfunction "P0.06_L1") (pintype "bidirectional"))
    )
    (net (code "46") (name "/P0.07") (class "Default")
      (node (ref "J1.26") (pin "0") (pinfunction "0_0") (pintype "passive"))
      (node (ref "U6") (pin "M2") (pinfunction "P0.07_M2") (pintype "bidirectional"))
    )
    (net (code "47") (name "/P0.12") (class "Default")
      (node (ref "J1.35") (pin "0") (pinfunction "0_0") (pintype "passive"))
      (node (ref "U6") (pin "U1") (pinfunction "P0.12_U1") (pintype "bidirectional"))
    )
    (net (code "48") (name "/P0.15") (class "Default")
      (node (ref "J1.40") (pin "0") (pinfunction "0_0") (pintype "passive"))
      (node (ref "U6") (pin "AD10") (pinfunction "P0.15_AD10") (pintype "bidirectional"))
    )
    (net (code "49") (name "/P0.18") (class "Default")
      (node (ref "J1.37") (pin "0") (pinfunction "0_0") (pintype "passive"))
      (node (ref "U6") (pin "AC13") (pinfunction "P0.18/RESET_AC13") (pintype "bidirectional"))
    )
    (net (code "50") (name "/P0.24") (class "Default")
      (node (ref "J1.42") (pin "0") (pinfunction "0_0") (pintype "passive"))
      (node (ref "U6") (pin "AD20") (pinfunction "P0.24_AD20") (pintype "bidirectional"))
    )
    (net (code "51") (name "/P0.26") (class "Default")
      (node (ref "J1.19") (pin "0") (pinfunction "0_0") (pintype "passive"))
      (node (ref "U6") (pin "G1") (pinfunction "P0.26_G1") (pintype "bidirectional"))
    )
    (net (code "52") (name "/P0.27") (class "Default")
      (node (ref "J1.20") (pin "0") (pinfunction "0_0") (pintype "passive"))
      (node (ref "U6") (pin "H2") (pinfunction "P0.27_H2") (pintype "bidirectional"))
    )
    (net (code "53") (name "/P0.30") (class "Default")
      (node (ref "J1.17") (pin "0") (pinfunction "0_0") (pintype "passive"))
      (node (ref "U6") (pin "B9") (pinfunction "P0.30/AIN6_B9") (pintype "bidirectional"))
    )
    (net (code "54") (name "/P0.31") (class "Default")
      (node (ref "J1.18") (pin "0") (pinfunction "0_0") (pintype "passive"))
      (node (ref "U6") (pin "A8") (pinfunction "P0.31/AIN7_A8") (pintype "bidirectional"))
    )
    (net (code "55") (name "/P1.11") (class "Default")
      (node (ref "J1.10") (pin "0") (pinfunction "0_0") (pintype "passive"))
      (node (ref "U6") (pin "B19") (pinfunction "P1.11_B19") (pintype "bidirectional"))
    )
    (net (code "56") (name "/P1.12") (class "Default")
      (node (ref "J1.11") (pin "0") (pinfunction "0_0") (pintype "passive"))
      (node (ref "U6") (pin "B17") (pinfunction "P1.12_B17") (pintype "bidirectional"))
    )
    (net (code "57") (name "/SWDCLK") (class "Default")
      (node (ref "J1.3") (pin "0") (pinfunction "0_0") (pintype "passive"))
      (node (ref "U6") (pin "AA24") (pinfunction "SWDCLK_AA24") (pintype "input"))
    )
    (net (code "58") (name "/SWDIO") (class "Default")
      (node (ref "J1.2") (pin "0") (pinfunction "0_0") (pintype "passive"))
      (node (ref "U6") (pin "AC24") (pinfunction "SWDIO_AC24") (pintype "bidirectional"))
    )
    (net (code "59") (name "/XC1") (class "Default")
      (node (ref "C75") (pin "2") (pinfunction "2_2") (pintype "passive"))
      (node (ref "U6") (pin "B24") (pinfunction "XC1_B24") (pintype "input"))
      (node (ref "X1") (pin "3") (pinfunction "3_3") (pintype "passive"))
    )
    (net (code "60") (name "/XC2") (class "Default")
      (node (ref "C74") (pin "2") (pinfunction "2_2") (pintype "passive"))
      (node (ref "U6") (pin "A23") (pinfunction "XC2_A23") (pintype "output"))
      (node (ref "X1") (pin "1") (pinfunction "1_1") (pintype "passive"))
    )
    (net (code "61") (name "GND") (class "Default")
      (node (ref "C107") (pin "1") (pinfunction "1_1") (pintype "passive"))
      (node (ref "C67") (pin "1") (pinfunction "1_1") (pintype "passive"))
      (node (ref "C68") (pin "1") (pinfunction "1_1") (pintype "passive"))
      (node (ref "C69") (pin "1") (pinfunction "1_1") (pintype "passive"))
      (node (ref "C70") (pin "1") (pinfunction "1_1") (pintype "passive"))
      (node (ref "C71") (pin "1") (pinfunction "1_1") (pintype "passive"))
      (node (ref "C72") (pin "1") (pinfunction "1_1") (pintype "passive"))
      (node (ref "C73") (pin "1") (pinfunction "1_1") (pintype "passive"))
      (node (ref "C74") (pin "1") (pinfunction "1_1") (pintype "passive"))
      (node (ref "C75") (pin "1") (pinfunction "1_1") (pintype "passive"))
      (node (ref "C76") (pin "1") (pinfunction "1_1") (pintype "passive"))
      (node (ref "C77") (pin "1") (pinfunction "1_1") (pintype "passive"))
      (node (ref "C78") (pin "1") (pinfunction "1_1") (pintype "passive"))
      (node (ref "C80") (pin "1") (pinfunction "1_1") (pintype "passive"))
      (node (ref "C86") (pin "1") (pinfunction "1_1") (pintype "passive"))
      (node (ref "C87") (pin "1") (pinfunction "1_1") (pintype "passive"))
      (node (ref "C90") (pin "1") (pinfunction "1_1") (pintype "passive"))
      (node (ref "C91") (pin "1") (pinfunction "1_1") (pintype "passive"))
      (node (ref "C94") (pin "1") (pinfunction "1_1") (pintype "passive"))
      (node (ref "C95") (pin "1") (pinfunction "1_1") (pintype "passive"))
      (node (ref "C96") (pin "1") (pinfunction "1_1") (pintype "passive"))
      (node (ref "C97") (pin "1") (pinfunction "1_1") (pintype "passive"))
      (node (ref "C98") (pin "1") (pinfunction "1_1") (pintype "passive"))
      (node (ref "C99") (pin "1") (pinfunction "1_1") (pintype "passive"))
      (node (ref "D2") (pin "A") (pinfunction "A_A") (pintype "passive"))
      (node (ref "J1.1") (pin "0") (pinfunction "0_0") (pintype "passive"))
      (node (ref "J1.14") (pin "0") (pinfunction "0_0") (pintype "passive"))
      (node (ref "J1.24") (pin "0") (pinfunction "0_0") (pintype "passive"))
      (node (ref "J1.33") (pin "0") (pinfunction "0_0") (pintype "passive"))
      (node (ref "J1.39") (pin "0") (pinfunction "0_0") (pintype "passive"))
      (node (ref "J1.47") (pin "0") (pinfunction "0_0") (pintype "passive"))
      (node (ref "J1.52") (pin "0") (pinfunction "0_0") (pintype "passive"))
      (node (ref "U6") (pin "74") (pinfunction "GND_74") (pintype "power_in"))
      (node (ref "U6") (pin "B7") (pinfunction "VSS_B7") (pintype "power_in"))
      (node (ref "U6") (pin "F23") (pinfunction "VSS_PA_F23") (pintype "power_in"))
      (node (ref "X1") (pin "2") (pinfunction "2_2") (pintype "passive"))
      (node (ref "X1") (pin "4") (pinfunction "4_4") (pintype "passive"))
    )
    (net (code "62") (name "Net-(L11-Pad1)") (class "Default")
      (node (ref "L11") (pin "1") (pinfunction "1_1") (pintype "passive"))
      (node (ref "L12") (pin "2") (pinfunction "2_2") (pintype "passive"))
    )
    (net (code "63") (name "Net-(U6-DEC2)") (class "Default")
      (node (ref "C86") (pin "2") (pinfunction "2_2") (pintype "passive"))
      (node (ref "U6") (pin "A18") (pinfunction "DEC2_A18") (pintype "power_in"))
    )
    (net (code "64") (name "Net-(U6-P0.00{slash}XL1)") (class "Default")
      (node (ref "C68") (pin "2") (pinfunction "2_2") (pintype "passive"))
      (node (ref "U6") (pin "D2") (pinfunction "P0.00/XL1_D2") (pintype "bidirectional"))
      (node (ref "X2") (pin "2") (pinfunction "2_2") (pintype "passive"))
    )
    (net (code "65") (name "Net-(U6-P0.01{slash}XL2)") (class "Default")
      (node (ref "C69") (pin "2") (pinfunction "2_2") (pintype "passive"))
      (node (ref "U6") (pin "F2") (pinfunction "P0.01/XL2_F2") (pintype "bidirectional"))
      (node (ref "X2") (pin "1") (pinfunction "1_1") (pintype "passive"))
    )
    (net (code "66") (name "VCC") (class "Default")
      (node (ref "D2") (pin "K") (pinfunction "K_K") (pintype "passive"))
      (node (ref "J1.23") (pin "0") (pinfunction "0_0") (pintype "passive"))
      (node (ref "R10") (pin "1") (pinfunction "1_1") (pintype "passive"))
      (node (ref "R11") (pin "1") (pinfunction "1_1") (pintype "passive"))
      (node (ref "R7") (pin "1") (pinfunction "1_1") (pintype "passive"))
      (node (ref "R8") (pin "1") (pinfunction "1_1") (pintype "passive"))
    )
    (net (code "67") (name "VCC_DEV") (class "Default")
      (node (ref "C107") (pin "2") (pinfunction "2_2") (pintype "passive"))
      (node (ref "C67") (pin "2") (pinfunction "2_2") (pintype "passive"))
      (node (ref "C71") (pin "2") (pinfunction "2_2") (pintype "passive"))
      (node (ref "C72") (pin "2") (pinfunction "2_2") (pintype "passive"))
      (node (ref "C80") (pin "2") (pinfunction "2_2") (pintype "passive"))
      (node (ref "C87") (pin "2") (pinfunction "2_2") (pintype "passive"))
      (node (ref "C90") (pin "2") (pinfunction "2_2") (pintype "passive"))
      (node (ref "C95") (pin "2") (pinfunction "2_2") (pintype "passive"))
      (node (ref "C97") (pin "2") (pinfunction "2_2") (pintype "passive"))
      (node (ref "C99") (pin "2") (pinfunction "2_2") (pintype "passive"))
      (node (ref "R10") (pin "2") (pinfunction "2_2") (pintype "passive"))
      (node (ref "TP15") (pin "1") (pinfunction "1_1") (pintype "passive"))
      (node (ref "U6") (pin "A22") (pinfunction "VDD_A22") (pintype "power_in"))
      (node (ref "U6") (pin "AD14") (pinfunction "VDD_AD14") (pintype "power_in"))
      (node (ref "U6") (pin "AD23") (pinfunction "VDD_AD23") (pintype "power_in"))
      (node (ref "U6") (pin "B1") (pinfunction "VDD_B1") (pintype "power_in"))
      (node (ref "U6") (pin "W1") (pinfunction "VDD_W1") (pintype "power_in"))
      (node (ref "U6") (pin "Y2") (pinfunction "VDDH_Y2") (pintype "power_in"))
    )
    (net (code "68") (name "VCC_USB") (class "Default")
      (node (ref "C96") (pin "2") (pinfunction "2_2") (pintype "passive"))
      (node (ref "J1.30") (pin "0") (pinfunction "0_0") (pintype "passive"))
      (node (ref "U6") (pin "AD2") (pinfunction "VBUS_AD2") (pintype "power_in"))
    )
    (net (code "69") (name "VDD_3V3_A") (class "Default")
      (node (ref "R8") (pin "2") (pinfunction "2_2") (pintype "passive"))
      (node (ref "TP17") (pin "1") (pinfunction "1_1") (pintype "passive"))
    )
    (net (code "70") (name "VDD_3V3_B") (class "Default")
      (node (ref "R7") (pin "2") (pinfunction "2_2") (pintype "passive"))
      (node (ref "TP16") (pin "1") (pinfunction "1_1") (pintype "passive"))
    )
    (net (code "71") (name "VDD_TCXO") (class "Default")
      (node (ref "R11") (pin "2") (pinfunction "2_2") (pintype "passive"))
      (node (ref "TP18") (pin "1") (pinfunction "1_1") (pintype "passive"))
    )
    (net (code "72") (name "unconnected-(U6-DCCH-PadAB2)") (class "Default")
      (node (ref "U6") (pin "AB2") (pinfunction "DCCH_AB2") (pintype "power_in"))
    )
  )
)
